# Sheet_1.net
KiCad netlist of a schematic drawn in EasyEDA
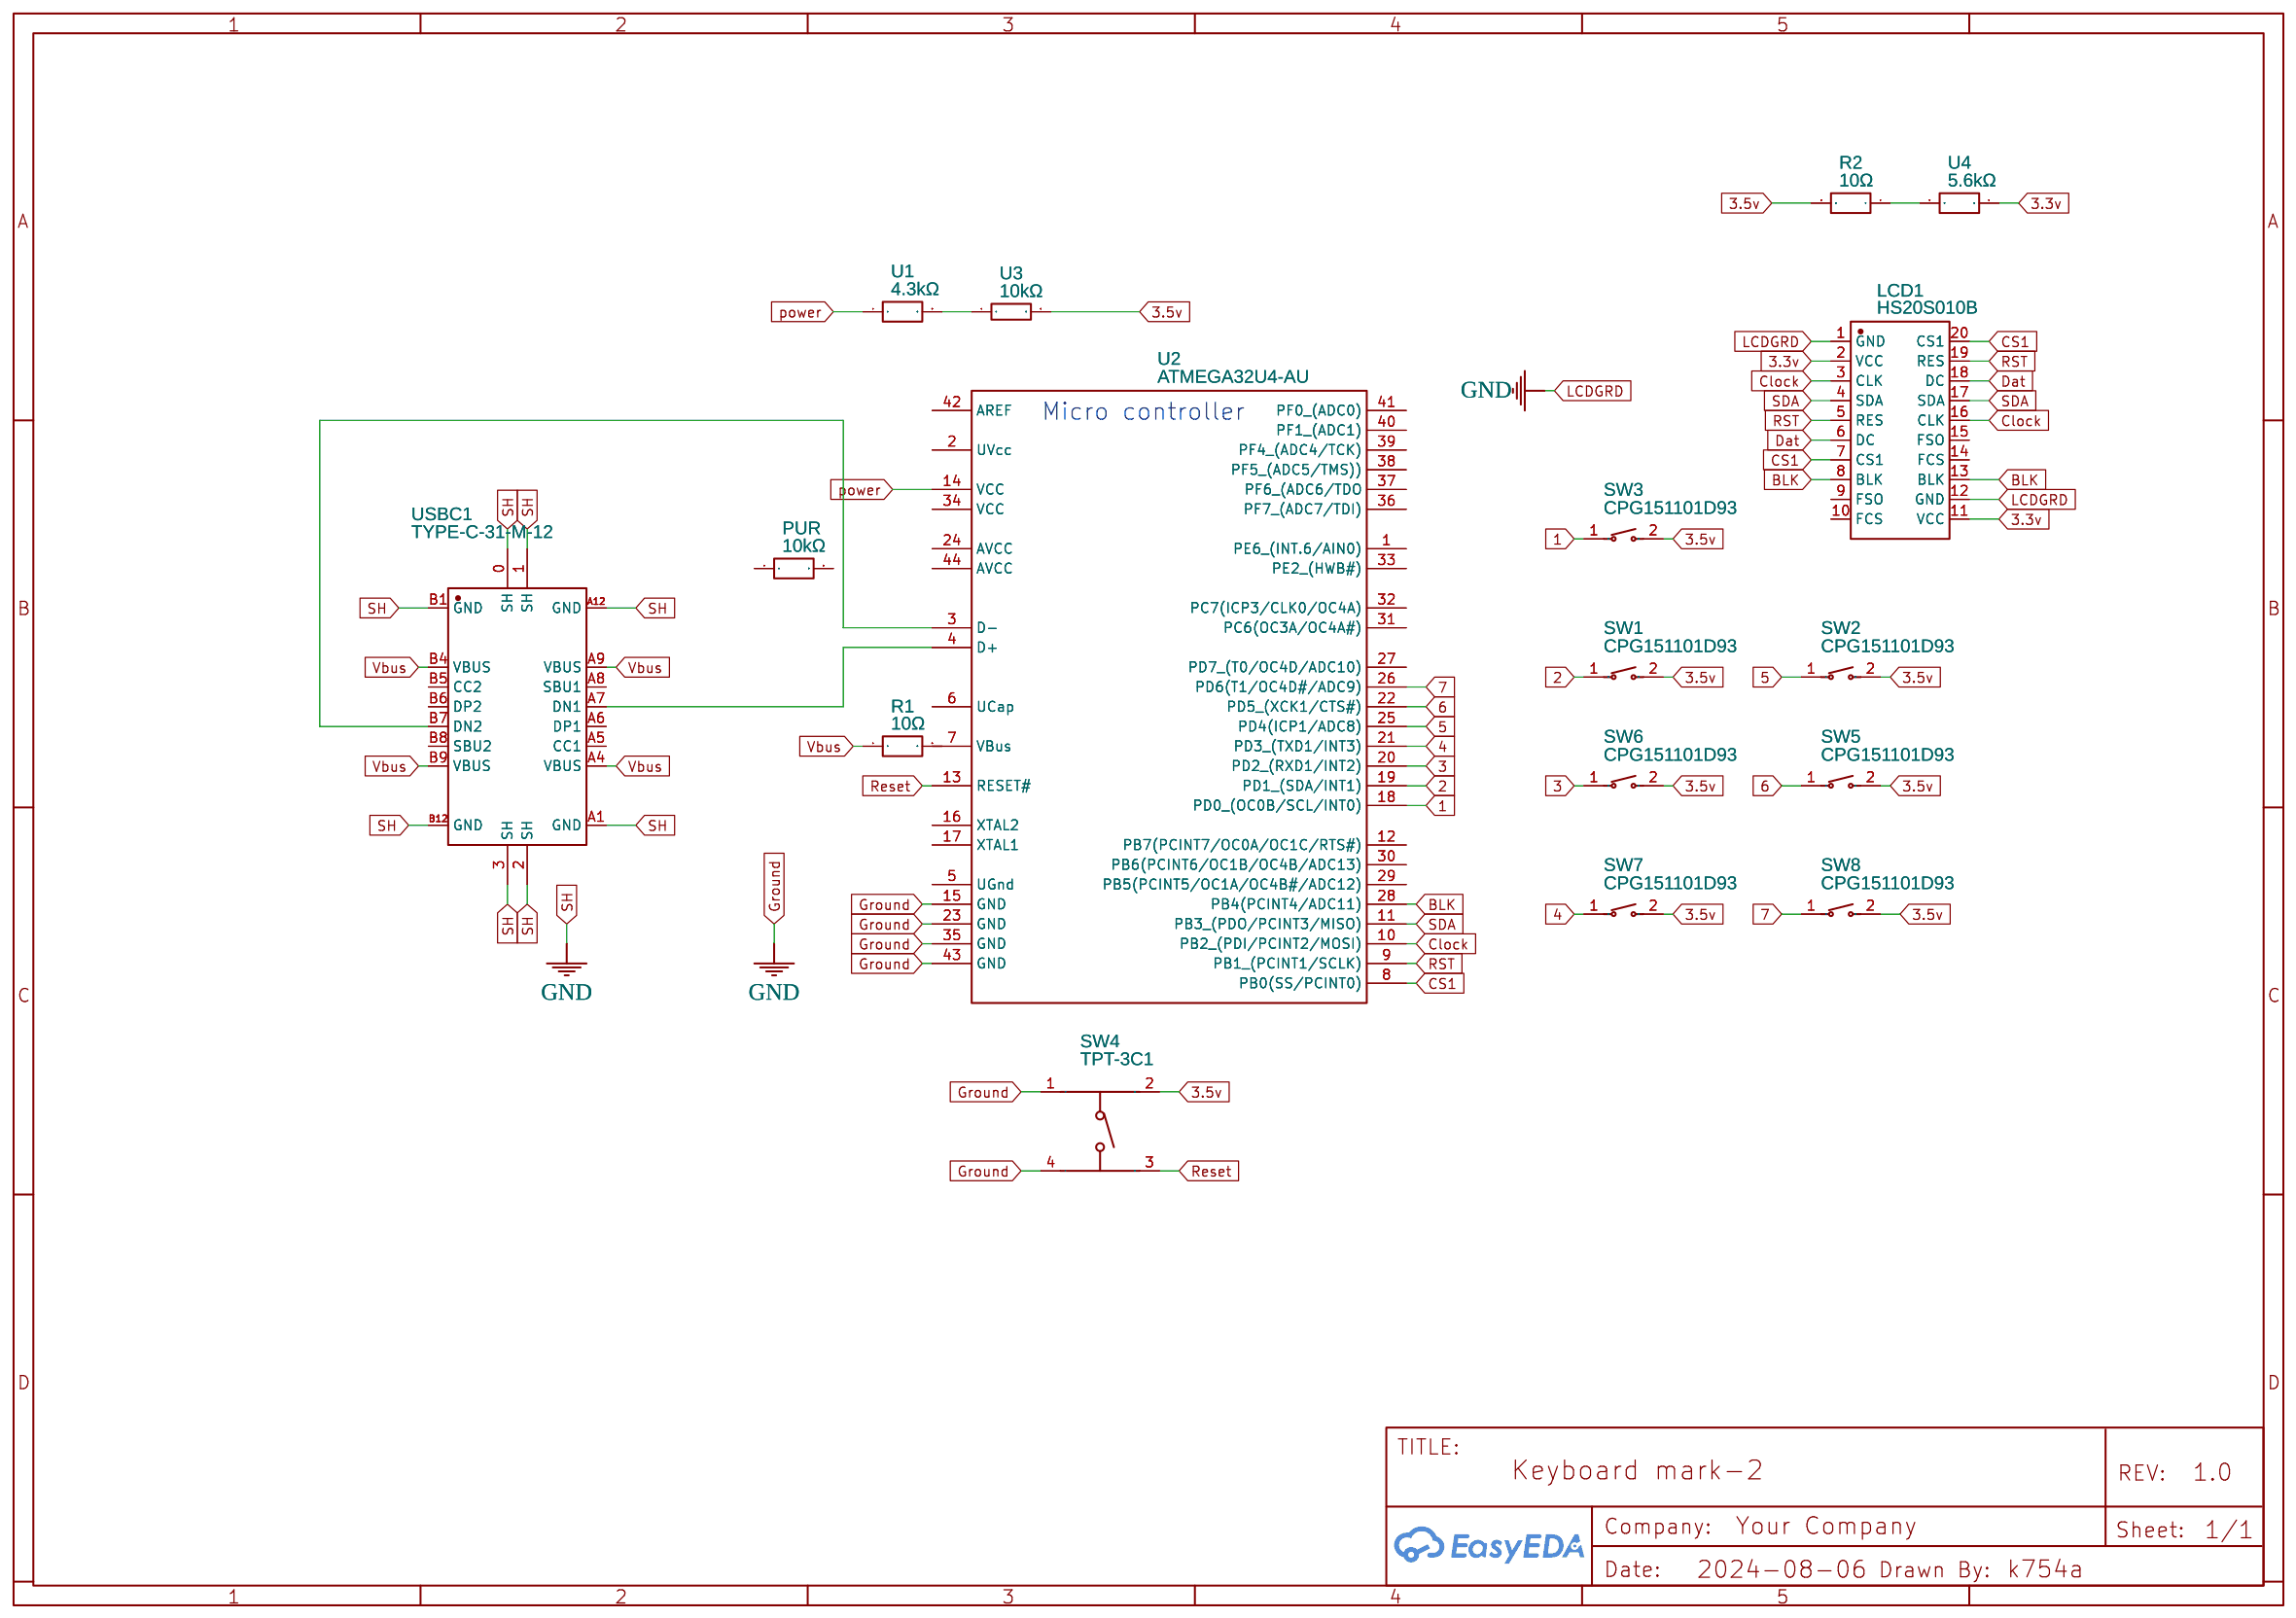
[diagram p0: schematic sheet]

(export (version "E")
  (design (tool "Eeschema 10.0.6"))
  (components
    (comp (ref "LCD1")
      (value "HS20S010B")
      (fields (field (name "Manufacturer") "HS(汉昇)"))
      (libsource (lib "") (part "HS20S010B"))
    )
    (comp (ref "PUR")
      (value "10kΩ")
      (fields (field (name "Manufacturer Part") "0402 ±1% 10K") (field (name "Manufacturer") "VO(翔胜)"))
      (libsource (lib "") (part "0402 ±1% 10K"))
    )
    (comp (ref "R1")
      (value "10Ω")
      (fields (field (name "Manufacturer Part") "CR1W-4K7±5%-TT63") (field (name "Manufacturer") "VO(翔胜)"))
      (libsource (lib "") (part "10Ω_1W"))
    )
    (comp (ref "R2")
      (value "10Ω")
      (fields (field (name "Manufacturer Part") "CR1W-4K7±5%-TT63") (field (name "Manufacturer") "VO(翔胜)"))
      (libsource (lib "") (part "10Ω_1W_1"))
    )
    (comp (ref "SW1")
      (value "CPG151101D93")
      (fields (field (name "Manufacturer") "Kailh(凯华)"))
      (libsource (lib "") (part "CPG151101D93"))
    )
    (comp (ref "SW2")
      (value "CPG151101D93")
      (fields (field (name "Manufacturer") "Kailh(凯华)"))
      (libsource (lib "") (part "CPG151101D93"))
    )
    (comp (ref "SW3")
      (value "CPG151101D93")
      (fields (field (name "Manufacturer") "Kailh(凯华)"))
      (libsource (lib "") (part "CPG151101D93"))
    )
    (comp (ref "SW4")
      (value "TPT-3C1")
      (fields (field (name "Manufacturer") "ROCPU Switches(台普)"))
      (libsource (lib "") (part "TPT-3C1"))
    )
    (comp (ref "SW5")
      (value "CPG151101D93")
      (fields (field (name "Manufacturer") "Kailh(凯华)"))
      (libsource (lib "") (part "CPG151101D93"))
    )
    (comp (ref "SW6")
      (value "CPG151101D93")
      (fields (field (name "Manufacturer") "Kailh(凯华)"))
      (libsource (lib "") (part "CPG151101D93"))
    )
    (comp (ref "SW7")
      (value "CPG151101D93")
      (fields (field (name "Manufacturer") "Kailh(凯华)"))
      (libsource (lib "") (part "CPG151101D93"))
    )
    (comp (ref "SW8")
      (value "CPG151101D93")
      (fields (field (name "Manufacturer") "Kailh(凯华)"))
      (libsource (lib "") (part "CPG151101D93"))
    )
    (comp (ref "U1")
      (value "4.3kΩ")
      (fields (field (name "Manufacturer Part") "CR1/8W-4K3±5%-OT52") (field (name "Manufacturer") "VO(翔胜)"))
      (libsource (lib "") (part "CR1/8W-4K3±5%-OT52"))
    )
    (comp (ref "U2")
      (value "ATMEGA32U4-AU")
      (fields (field (name "Manufacturer") "MICROCHIP(美国微芯)"))
      (libsource (lib "") (part "ATMEGA32U4-AU"))
    )
    (comp (ref "U3")
      (value "10kΩ")
      (fields (field (name "Manufacturer Part") "HV73V1JTTD1002F") (field (name "Manufacturer") "KOA"))
      (libsource (lib "") (part "HV73V1JTTD1002F"))
    )
    (comp (ref "U4")
      (value "5.6kΩ")
      (fields (field (name "Manufacturer Part") "23J5K6E") (field (name "Manufacturer") "Ohmite"))
      (libsource (lib "") (part "23J5K6E"))
    )
    (comp (ref "USBC1")
      (value "TYPE-C-31-M-12")
      (fields (field (name "Manufacturer") "韩国韩荣"))
      (libsource (lib "") (part "TYPE-C-31-M-12"))
    )
  )
  (nets
    (net (code "1") (name "1") (class "Default")
      (node (ref "SW3") (pin "1") (pinfunction "1_1") (pintype "unspecified"))
      (node (ref "U2") (pin "18") (pinfunction "PD0_(OC0B/SCL/INT0)_18") (pintype "bidirectional"))
    )
    (net (code "2") (name "2") (class "Default")
      (node (ref "SW1") (pin "1") (pinfunction "1_1") (pintype "unspecified"))
      (node (ref "U2") (pin "19") (pinfunction "PD1_(SDA/INT1)_19") (pintype "bidirectional"))
    )
    (net (code "3") (name "3") (class "Default")
      (node (ref "SW6") (pin "1") (pinfunction "1_1") (pintype "unspecified"))
      (node (ref "U2") (pin "20") (pinfunction "PD2_(RXD1/INT2)_20") (pintype "bidirectional"))
    )
    (net (code "4") (name "3.3v") (class "Default")
      (node (ref "LCD1") (pin "11") (pinfunction "VCC_11") (pintype "unspecified"))
      (node (ref "LCD1") (pin "2") (pinfunction "VCC_2") (pintype "unspecified"))
      (node (ref "U4") (pin "1") (pinfunction "1_1") (pintype "unspecified"))
    )
    (net (code "5") (name "3.5v") (class "Default")
      (node (ref "R2") (pin "2") (pinfunction "2_2") (pintype "unspecified"))
      (node (ref "SW1") (pin "2") (pinfunction "2_2") (pintype "unspecified"))
      (node (ref "SW2") (pin "2") (pinfunction "2_2") (pintype "unspecified"))
      (node (ref "SW3") (pin "2") (pinfunction "2_2") (pintype "unspecified"))
      (node (ref "SW4") (pin "2") (pinfunction "2_2") (pintype "unspecified"))
      (node (ref "SW5") (pin "2") (pinfunction "2_2") (pintype "unspecified"))
      (node (ref "SW6") (pin "2") (pinfunction "2_2") (pintype "unspecified"))
      (node (ref "SW7") (pin "2") (pinfunction "2_2") (pintype "unspecified"))
      (node (ref "SW8") (pin "2") (pinfunction "2_2") (pintype "unspecified"))
      (node (ref "U3") (pin "2") (pinfunction "2_2") (pintype "unspecified"))
    )
    (net (code "6") (name "4") (class "Default")
      (node (ref "SW7") (pin "1") (pinfunction "1_1") (pintype "unspecified"))
      (node (ref "U2") (pin "21") (pinfunction "PD3_(TXD1/INT3)_21") (pintype "bidirectional"))
    )
    (net (code "7") (name "5") (class "Default")
      (node (ref "SW2") (pin "1") (pinfunction "1_1") (pintype "unspecified"))
      (node (ref "U2") (pin "25") (pinfunction "PD4(ICP1/ADC8)_25") (pintype "bidirectional"))
    )
    (net (code "8") (name "6") (class "Default")
      (node (ref "SW5") (pin "1") (pinfunction "1_1") (pintype "unspecified"))
      (node (ref "U2") (pin "22") (pinfunction "PD5_(XCK1/CTS#)_22") (pintype "bidirectional"))
    )
    (net (code "9") (name "7") (class "Default")
      (node (ref "SW8") (pin "1") (pinfunction "1_1") (pintype "unspecified"))
      (node (ref "U2") (pin "26") (pinfunction "PD6(T1/OC4D#/ADC9)_26") (pintype "bidirectional"))
    )
    (net (code "10") (name "BLK") (class "Default")
      (node (ref "LCD1") (pin "13") (pinfunction "BLK_13") (pintype "unspecified"))
      (node (ref "LCD1") (pin "8") (pinfunction "BLK_8") (pintype "unspecified"))
      (node (ref "U2") (pin "28") (pinfunction "PB4(PCINT4/ADC11)_28") (pintype "bidirectional"))
    )
    (net (code "11") (name "CS1") (class "Default")
      (node (ref "LCD1") (pin "20") (pinfunction "CS1_20") (pintype "unspecified"))
      (node (ref "LCD1") (pin "7") (pinfunction "CS1_7") (pintype "unspecified"))
      (node (ref "U2") (pin "8") (pinfunction "PB0(SS/PCINT0)_8") (pintype "bidirectional"))
    )
    (net (code "12") (name "Clock") (class "Default")
      (node (ref "LCD1") (pin "16") (pinfunction "CLK_16") (pintype "unspecified"))
      (node (ref "LCD1") (pin "3") (pinfunction "CLK_3") (pintype "unspecified"))
      (node (ref "U2") (pin "10") (pinfunction "PB2_(PDI/PCINT2/MOSI)_10") (pintype "bidirectional"))
    )
    (net (code "13") (name "Dat") (class "Default")
      (node (ref "LCD1") (pin "18") (pinfunction "DC_18") (pintype "unspecified"))
      (node (ref "LCD1") (pin "6") (pinfunction "DC_6") (pintype "unspecified"))
    )
    (net (code "14") (name "Ground") (class "Default")
      (node (ref "LCD1") (pin "1") (pinfunction "GND_1") (pintype "unspecified"))
      (node (ref "LCD1") (pin "12") (pinfunction "GND_12") (pintype "unspecified"))
      (node (ref "SW4") (pin "1") (pinfunction "1_1") (pintype "unspecified"))
      (node (ref "SW4") (pin "4") (pinfunction "4_4") (pintype "unspecified"))
      (node (ref "U2") (pin "15") (pinfunction "GND_15") (pintype "passive"))
      (node (ref "U2") (pin "23") (pinfunction "GND_23") (pintype "passive"))
      (node (ref "U2") (pin "35") (pinfunction "GND_35") (pintype "passive"))
      (node (ref "U2") (pin "43") (pinfunction "GND_43") (pintype "passive"))
      (node (ref "USBC1") (pin "0") (pinfunction "SH_0") (pintype "unspecified"))
      (node (ref "USBC1") (pin "1") (pinfunction "SH_1") (pintype "unspecified"))
      (node (ref "USBC1") (pin "2") (pinfunction "SH_2") (pintype "unspecified"))
      (node (ref "USBC1") (pin "3") (pinfunction "SH_3") (pintype "unspecified"))
      (node (ref "USBC1") (pin "A1") (pinfunction "GND_A1") (pintype "unspecified"))
      (node (ref "USBC1") (pin "A12") (pinfunction "GND_A12") (pintype "unspecified"))
      (node (ref "USBC1") (pin "B1") (pinfunction "GND_B1") (pintype "unspecified"))
      (node (ref "USBC1") (pin "B12") (pinfunction "GND_B12") (pintype "unspecified"))
    )
    (net (code "15") (name "Net-(R2-Pad1)") (class "Default")
      (node (ref "R2") (pin "1") (pinfunction "1_1") (pintype "unspecified"))
      (node (ref "U4") (pin "2") (pinfunction "2_2") (pintype "unspecified"))
    )
    (net (code "16") (name "Net-(U1-Pad2)") (class "Default")
      (node (ref "U1") (pin "2") (pinfunction "2_2") (pintype "unspecified"))
      (node (ref "U3") (pin "1") (pinfunction "1_1") (pintype "unspecified"))
    )
    (net (code "17") (name "Net-(U2-D+)") (class "Default")
      (node (ref "U2") (pin "4") (pinfunction "D+_4") (pintype "bidirectional"))
      (node (ref "USBC1") (pin "A7") (pinfunction "DN1_A7") (pintype "unspecified"))
    )
    (net (code "18") (name "Net-(U2-D-)") (class "Default")
      (node (ref "U2") (pin "3") (pinfunction "D-_3") (pintype "bidirectional"))
      (node (ref "USBC1") (pin "B7") (pinfunction "DN2_B7") (pintype "unspecified"))
    )
    (net (code "19") (name "Net-(U2-VBus)") (class "Default")
      (node (ref "R1") (pin "2") (pinfunction "2_2") (pintype "unspecified"))
      (node (ref "U2") (pin "7") (pinfunction "VBus_7") (pintype "unspecified"))
    )
    (net (code "20") (name "RST") (class "Default")
      (node (ref "LCD1") (pin "19") (pinfunction "RES_19") (pintype "unspecified"))
      (node (ref "LCD1") (pin "5") (pinfunction "RES_5") (pintype "unspecified"))
      (node (ref "U2") (pin "9") (pinfunction "PB1_(PCINT1/SCLK)_9") (pintype "bidirectional"))
    )
    (net (code "21") (name "Reset") (class "Default")
      (node (ref "SW4") (pin "3") (pinfunction "3_3") (pintype "unspecified"))
      (node (ref "U2") (pin "13") (pinfunction "RESET#_13") (pintype "unspecified"))
    )
    (net (code "22") (name "SDA") (class "Default")
      (node (ref "LCD1") (pin "17") (pinfunction "SDA_17") (pintype "unspecified"))
      (node (ref "LCD1") (pin "4") (pinfunction "SDA_4") (pintype "unspecified"))
      (node (ref "U2") (pin "11") (pinfunction "PB3_(PDO/PCINT3/MISO)_11") (pintype "bidirectional"))
    )
    (net (code "23") (name "Vbus") (class "Default")
      (node (ref "R1") (pin "1") (pinfunction "1_1") (pintype "unspecified"))
      (node (ref "USBC1") (pin "A4") (pinfunction "VBUS_A4") (pintype "unspecified"))
      (node (ref "USBC1") (pin "A9") (pinfunction "VBUS_A9") (pintype "unspecified"))
      (node (ref "USBC1") (pin "B4") (pinfunction "VBUS_B4") (pintype "unspecified"))
      (node (ref "USBC1") (pin "B9") (pinfunction "VBUS_B9") (pintype "unspecified"))
    )
    (net (code "24") (name "power") (class "Default")
      (node (ref "U1") (pin "1") (pinfunction "1_1") (pintype "unspecified"))
      (node (ref "U2") (pin "14") (pinfunction "VCC_14") (pintype "passive"))
    )
    (net (code "25") (name "unconnected-(LCD1-FCS-Pad10)") (class "Default")
      (node (ref "LCD1") (pin "10") (pinfunction "FCS_10") (pintype "unspecified"))
    )
    (net (code "26") (name "unconnected-(LCD1-FCS-Pad14)") (class "Default")
      (node (ref "LCD1") (pin "14") (pinfunction "FCS_14") (pintype "unspecified"))
    )
    (net (code "27") (name "unconnected-(LCD1-FSO-Pad9)") (class "Default")
      (node (ref "LCD1") (pin "9") (pinfunction "FSO_9") (pintype "unspecified"))
    )
    (net (code "28") (name "unconnected-(LCD1-FSO-Pad15)") (class "Default")
      (node (ref "LCD1") (pin "15") (pinfunction "FSO_15") (pintype "unspecified"))
    )
    (net (code "29") (name "unconnected-(PUR-Pad1)") (class "Default")
      (node (ref "PUR") (pin "1") (pinfunction "1_1") (pintype "unspecified"))
    )
    (net (code "30") (name "unconnected-(PUR-Pad2)") (class "Default")
      (node (ref "PUR") (pin "2") (pinfunction "2_2") (pintype "unspecified"))
    )
    (net (code "31") (name "unconnected-(U2-AREF-Pad42)") (class "Default")
      (node (ref "U2") (pin "42") (pinfunction "AREF_42") (pintype "unspecified"))
    )
    (net (code "32") (name "unconnected-(U2-AVCC-Pad24)") (class "Default")
      (node (ref "U2") (pin "24") (pinfunction "AVCC_24") (pintype "passive"))
    )
    (net (code "33") (name "unconnected-(U2-AVCC-Pad44)") (class "Default")
      (node (ref "U2") (pin "44") (pinfunction "AVCC_44") (pintype "passive"))
    )
    (net (code "34") (name "unconnected-(U2-PB5(PCINT5{slash}OC1A{slash}OC4B#{slash}ADC12)-Pad29)") (class "Default")
      (node (ref "U2") (pin "29") (pinfunction "PB5(PCINT5/OC1A/OC4B#/ADC12)_29") (pintype "bidirectional"))
    )
    (net (code "35") (name "unconnected-(U2-PB6(PCINT6{slash}OC1B{slash}OC4B{slash}ADC13)-Pad30)") (class "Default")
      (node (ref "U2") (pin "30") (pinfunction "PB6(PCINT6/OC1B/OC4B/ADC13)_30") (pintype "bidirectional"))
    )
    (net (code "36") (name "unconnected-(U2-PB7(PCINT7{slash}OC0A{slash}OC1C{slash}RTS#)-Pad12)") (class "Default")
      (node (ref "U2") (pin "12") (pinfunction "PB7(PCINT7/OC0A/OC1C/RTS#)_12") (pintype "bidirectional"))
    )
    (net (code "37") (name "unconnected-(U2-PC6(OC3A{slash}OC4A#)-Pad31)") (class "Default")
      (node (ref "U2") (pin "31") (pinfunction "PC6(OC3A/OC4A#)_31") (pintype "bidirectional"))
    )
    (net (code "38") (name "unconnected-(U2-PC7(ICP3{slash}CLK0{slash}OC4A)-Pad32)") (class "Default")
      (node (ref "U2") (pin "32") (pinfunction "PC7(ICP3/CLK0/OC4A)_32") (pintype "bidirectional"))
    )
    (net (code "39") (name "unconnected-(U2-PD7_(T0{slash}OC4D{slash}ADC10)-Pad27)") (class "Default")
      (node (ref "U2") (pin "27") (pinfunction "PD7_(T0/OC4D/ADC10)_27") (pintype "bidirectional"))
    )
    (net (code "40") (name "unconnected-(U2-PE2_(HWB#)-Pad33)") (class "Default")
      (node (ref "U2") (pin "33") (pinfunction "PE2_(HWB#)_33") (pintype "bidirectional"))
    )
    (net (code "41") (name "unconnected-(U2-PE6_(INT.6{slash}AIN0)-Pad1)") (class "Default")
      (node (ref "U2") (pin "1") (pinfunction "PE6_(INT.6/AIN0)_1") (pintype "bidirectional"))
    )
    (net (code "42") (name "unconnected-(U2-PF0_(ADC0)-Pad41)") (class "Default")
      (node (ref "U2") (pin "41") (pinfunction "PF0_(ADC0)_41") (pintype "bidirectional"))
    )
    (net (code "43") (name "unconnected-(U2-PF1_(ADC1)-Pad40)") (class "Default")
      (node (ref "U2") (pin "40") (pinfunction "PF1_(ADC1)_40") (pintype "bidirectional"))
    )
    (net (code "44") (name "unconnected-(U2-PF4_(ADC4{slash}TCK)-Pad39)") (class "Default")
      (node (ref "U2") (pin "39") (pinfunction "PF4_(ADC4/TCK)_39") (pintype "bidirectional"))
    )
    (net (code "45") (name "unconnected-(U2-PF5_(ADC5{slash}TMS))-Pad38)") (class "Default")
      (node (ref "U2") (pin "38") (pinfunction "PF5_(ADC5/TMS))_38") (pintype "bidirectional"))
    )
    (net (code "46") (name "unconnected-(U2-PF6_(ADC6{slash}TDO-Pad37)") (class "Default")
      (node (ref "U2") (pin "37") (pinfunction "PF6_(ADC6/TDO_37") (pintype "bidirectional"))
    )
    (net (code "47") (name "unconnected-(U2-PF7_(ADC7{slash}TDI)-Pad36)") (class "Default")
      (node (ref "U2") (pin "36") (pinfunction "PF7_(ADC7/TDI)_36") (pintype "bidirectional"))
    )
    (net (code "48") (name "unconnected-(U2-UCap-Pad6)") (class "Default")
      (node (ref "U2") (pin "6") (pinfunction "UCap_6") (pintype "unspecified"))
    )
    (net (code "49") (name "unconnected-(U2-UGnd-Pad5)") (class "Default")
      (node (ref "U2") (pin "5") (pinfunction "UGnd_5") (pintype "passive"))
    )
    (net (code "50") (name "unconnected-(U2-UVcc-Pad2)") (class "Default")
      (node (ref "U2") (pin "2") (pinfunction "UVcc_2") (pintype "passive"))
    )
    (net (code "51") (name "unconnected-(U2-VCC-Pad34)") (class "Default")
      (node (ref "U2") (pin "34") (pinfunction "VCC_34") (pintype "passive"))
    )
    (net (code "52") (name "unconnected-(U2-XTAL1-Pad17)") (class "Default")
      (node (ref "U2") (pin "17") (pinfunction "XTAL1_17") (pintype "unspecified"))
    )
    (net (code "53") (name "unconnected-(U2-XTAL2-Pad16)") (class "Default")
      (node (ref "U2") (pin "16") (pinfunction "XTAL2_16") (pintype "output"))
    )
    (net (code "54") (name "unconnected-(USBC1-CC1-PadA5)") (class "Default")
      (node (ref "USBC1") (pin "A5") (pinfunction "CC1_A5") (pintype "unspecified"))
    )
    (net (code "55") (name "unconnected-(USBC1-CC2-PadB5)") (class "Default")
      (node (ref "USBC1") (pin "B5") (pinfunction "CC2_B5") (pintype "unspecified"))
    )
    (net (code "56") (name "unconnected-(USBC1-DP1-PadA6)") (class "Default")
      (node (ref "USBC1") (pin "A6") (pinfunction "DP1_A6") (pintype "unspecified"))
    )
    (net (code "57") (name "unconnected-(USBC1-DP2-PadB6)") (class "Default")
      (node (ref "USBC1") (pin "B6") (pinfunction "DP2_B6") (pintype "unspecified"))
    )
    (net (code "58") (name "unconnected-(USBC1-SBU1-PadA8)") (class "Default")
      (node (ref "USBC1") (pin "A8") (pinfunction "SBU1_A8") (pintype "unspecified"))
    )
    (net (code "59") (name "unconnected-(USBC1-SBU2-PadB8)") (class "Default")
      (node (ref "USBC1") (pin "B8") (pinfunction "SBU2_B8") (pintype "unspecified"))
    )
  )
)
